# M_16PWM.net
KiCad netlist of a schematic drawn in EAGLE
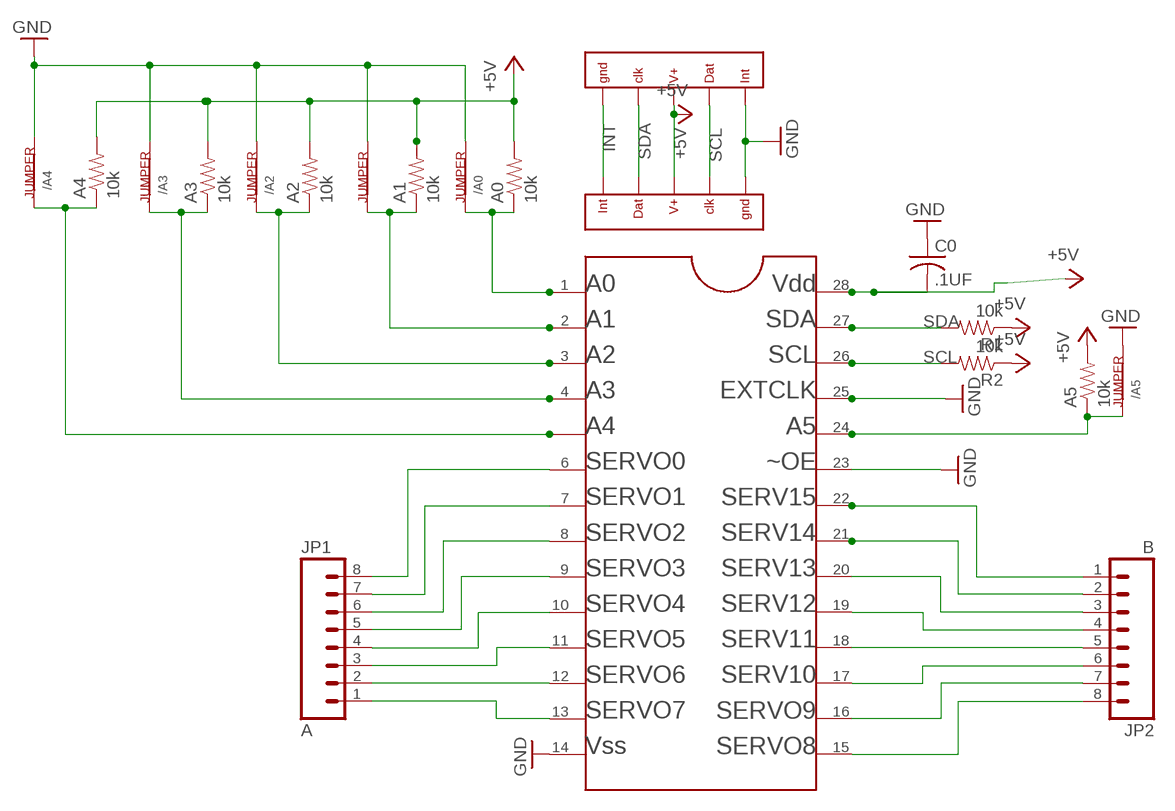
[diagram p0: schematic, sheet 1]

(export (version "E")
  (design (tool "Eeschema 10.0.6"))
  (components
    (comp (ref "/A0")
      (value "JUMPER")
      (footprint "eagle-import:JUMPER")
      (libsource (lib "eagle-import") (part "JUMPER"))
    )
    (comp (ref "/A1")
      (value "JUMPER")
      (footprint "eagle-import:JUMPER")
      (libsource (lib "eagle-import") (part "JUMPER"))
    )
    (comp (ref "/A2")
      (value "JUMPER")
      (footprint "eagle-import:JUMPER")
      (libsource (lib "eagle-import") (part "JUMPER"))
    )
    (comp (ref "/A3")
      (value "JUMPER")
      (footprint "eagle-import:JUMPER")
      (libsource (lib "eagle-import") (part "JUMPER"))
    )
    (comp (ref "/A4")
      (value "JUMPER")
      (footprint "eagle-import:JUMPER")
      (libsource (lib "eagle-import") (part "JUMPER"))
    )
    (comp (ref "/A5")
      (value "JUMPER")
      (footprint "eagle-import:JUMPER")
      (libsource (lib "eagle-import") (part "JUMPER"))
    )
    (comp (ref "A0")
      (value "10k")
      (footprint "eagle-import:0402-RES")
      (libsource (lib "eagle-import") (part "RESISTOR0402-RES"))
    )
    (comp (ref "A1")
      (value "10k")
      (footprint "eagle-import:0402-RES")
      (libsource (lib "eagle-import") (part "RESISTOR0402-RES"))
    )
    (comp (ref "A2")
      (value "10k")
      (footprint "eagle-import:0402-RES")
      (libsource (lib "eagle-import") (part "RESISTOR0402-RES"))
    )
    (comp (ref "A3")
      (value "10k")
      (footprint "eagle-import:0402-RES")
      (libsource (lib "eagle-import") (part "RESISTOR0402-RES"))
    )
    (comp (ref "A4")
      (value "10k")
      (footprint "eagle-import:0402-RES")
      (libsource (lib "eagle-import") (part "RESISTOR0402-RES"))
    )
    (comp (ref "A5")
      (value "10k")
      (footprint "eagle-import:0402-RES")
      (libsource (lib "eagle-import") (part "RESISTOR0402-RES"))
    )
    (comp (ref "C0")
      (value ".1UF")
      (footprint "eagle-import:C0603")
      (libsource (lib "eagle-import") (part "C-USC0603"))
    )
    (comp (ref "JP1")
      (value "A")
      (footprint "eagle-import:1X08")
      (libsource (lib "eagle-import") (part "M081X08"))
    )
    (comp (ref "JP2")
      (value "B")
      (footprint "eagle-import:1X08")
      (libsource (lib "eagle-import") (part "M081X08"))
    )
    (comp (ref "R1")
      (value "10k")
      (footprint "eagle-import:0402-RES")
      (libsource (lib "eagle-import") (part "RESISTOR0402-RES"))
    )
    (comp (ref "R2")
      (value "10k")
      (footprint "eagle-import:0402-RES")
      (libsource (lib "eagle-import") (part "RESISTOR0402-RES"))
    )
    (comp (ref "U$1")
      (value "PCA9685PW")
      (footprint "eagle-import:TSSOP28")
      (libsource (lib "eagle-import") (part "PCA9685PW"))
    )
    (comp (ref "U$2")
      (value "050-5")
      (footprint "eagle-import:050-5")
      (libsource (lib "eagle-import") (part "050-5"))
    )
    (comp (ref "U$3")
      (value "050-5")
      (footprint "eagle-import:050-5")
      (libsource (lib "eagle-import") (part "050-5"))
    )
  )
  (nets
    (net (code "1") (name "+5V") (class "Default")
      (node (ref "A0") (pin "2") (pinfunction "2_2") (pintype "passive"))
      (node (ref "A1") (pin "2") (pinfunction "2_2") (pintype "passive"))
      (node (ref "A2") (pin "2") (pinfunction "2_2") (pintype "passive"))
      (node (ref "A3") (pin "2") (pinfunction "2_2") (pintype "passive"))
      (node (ref "A4") (pin "2") (pinfunction "2_2") (pintype "passive"))
      (node (ref "A5") (pin "2") (pinfunction "2_2") (pintype "passive"))
      (node (ref "C0") (pin "2") (pinfunction "2_2") (pintype "passive"))
      (node (ref "R1") (pin "1") (pinfunction "1_1") (pintype "passive"))
      (node (ref "R2") (pin "1") (pinfunction "1_1") (pintype "passive"))
      (node (ref "U$1") (pin "28") (pinfunction "P$28_28") (pintype "bidirectional"))
      (node (ref "U$2") (pin "P$3") (pinfunction "P$3_P$3") (pintype "bidirectional"))
      (node (ref "U$3") (pin "P$3") (pinfunction "P$3_P$3") (pintype "bidirectional"))
    )
    (net (code "2") (name "/INT") (class "Default")
      (node (ref "U$2") (pin "P$1") (pinfunction "P$1_P$1") (pintype "bidirectional"))
      (node (ref "U$3") (pin "P$5") (pinfunction "P$5_P$5") (pintype "bidirectional"))
    )
    (net (code "3") (name "/SCL") (class "Default")
      (node (ref "R2") (pin "2") (pinfunction "2_2") (pintype "passive"))
      (node (ref "U$1") (pin "26") (pinfunction "P$26_26") (pintype "bidirectional"))
      (node (ref "U$2") (pin "P$4") (pinfunction "P$4_P$4") (pintype "bidirectional"))
      (node (ref "U$3") (pin "P$2") (pinfunction "P$2_P$2") (pintype "bidirectional"))
    )
    (net (code "4") (name "/SDA") (class "Default")
      (node (ref "R1") (pin "2") (pinfunction "2_2") (pintype "passive"))
      (node (ref "U$1") (pin "27") (pinfunction "P$27_27") (pintype "bidirectional"))
      (node (ref "U$2") (pin "P$2") (pinfunction "P$2_P$2") (pintype "bidirectional"))
      (node (ref "U$3") (pin "P$4") (pinfunction "P$4_P$4") (pintype "bidirectional"))
    )
    (net (code "5") (name "GND") (class "Default")
      (node (ref "/A0") (pin "2") (pinfunction "P$2_2") (pintype "bidirectional"))
      (node (ref "/A1") (pin "2") (pinfunction "P$2_2") (pintype "bidirectional"))
      (node (ref "/A2") (pin "2") (pinfunction "P$2_2") (pintype "bidirectional"))
      (node (ref "/A3") (pin "2") (pinfunction "P$2_2") (pintype "bidirectional"))
      (node (ref "/A4") (pin "2") (pinfunction "P$2_2") (pintype "bidirectional"))
      (node (ref "/A5") (pin "2") (pinfunction "P$2_2") (pintype "bidirectional"))
      (node (ref "C0") (pin "1") (pinfunction "1_1") (pintype "passive"))
      (node (ref "U$1") (pin "14") (pinfunction "P$14_14") (pintype "bidirectional"))
      (node (ref "U$1") (pin "23") (pinfunction "P$23_23") (pintype "bidirectional"))
      (node (ref "U$1") (pin "25") (pinfunction "P$25_25") (pintype "bidirectional"))
      (node (ref "U$2") (pin "P$5") (pinfunction "P$5_P$5") (pintype "bidirectional"))
      (node (ref "U$3") (pin "P$1") (pinfunction "P$1_P$1") (pintype "bidirectional"))
    )
    (net (code "6") (name "Net-(/A0-P$1)") (class "Default")
      (node (ref "/A0") (pin "1") (pinfunction "P$1_1") (pintype "bidirectional"))
      (node (ref "A0") (pin "1") (pinfunction "1_1") (pintype "passive"))
      (node (ref "U$1") (pin "1") (pinfunction "P$1_1") (pintype "bidirectional"))
    )
    (net (code "7") (name "Net-(/A1-P$1)") (class "Default")
      (node (ref "/A1") (pin "1") (pinfunction "P$1_1") (pintype "bidirectional"))
      (node (ref "A1") (pin "1") (pinfunction "1_1") (pintype "passive"))
      (node (ref "U$1") (pin "2") (pinfunction "P$2_2") (pintype "bidirectional"))
    )
    (net (code "8") (name "Net-(/A2-P$1)") (class "Default")
      (node (ref "/A2") (pin "1") (pinfunction "P$1_1") (pintype "bidirectional"))
      (node (ref "A2") (pin "1") (pinfunction "1_1") (pintype "passive"))
      (node (ref "U$1") (pin "3") (pinfunction "P$3_3") (pintype "bidirectional"))
    )
    (net (code "9") (name "Net-(/A3-P$1)") (class "Default")
      (node (ref "/A3") (pin "1") (pinfunction "P$1_1") (pintype "bidirectional"))
      (node (ref "A3") (pin "1") (pinfunction "1_1") (pintype "passive"))
      (node (ref "U$1") (pin "4") (pinfunction "P$4_4") (pintype "bidirectional"))
    )
    (net (code "10") (name "Net-(/A4-P$1)") (class "Default")
      (node (ref "/A4") (pin "1") (pinfunction "P$1_1") (pintype "bidirectional"))
      (node (ref "A4") (pin "1") (pinfunction "1_1") (pintype "passive"))
      (node (ref "U$1") (pin "5") (pinfunction "P$5_5") (pintype "bidirectional"))
    )
    (net (code "11") (name "Net-(/A5-P$1)") (class "Default")
      (node (ref "/A5") (pin "1") (pinfunction "P$1_1") (pintype "bidirectional"))
      (node (ref "A5") (pin "1") (pinfunction "1_1") (pintype "passive"))
      (node (ref "U$1") (pin "24") (pinfunction "P$24_24") (pintype "bidirectional"))
    )
    (net (code "12") (name "Net-(U$1-P$6)") (class "Default")
      (node (ref "JP1") (pin "8") (pinfunction "8_8") (pintype "passive"))
      (node (ref "U$1") (pin "6") (pinfunction "P$6_6") (pintype "bidirectional"))
    )
    (net (code "13") (name "Net-(U$1-P$7)") (class "Default")
      (node (ref "JP1") (pin "7") (pinfunction "7_7") (pintype "passive"))
      (node (ref "U$1") (pin "7") (pinfunction "P$7_7") (pintype "bidirectional"))
    )
    (net (code "14") (name "Net-(U$1-P$8)") (class "Default")
      (node (ref "JP1") (pin "6") (pinfunction "6_6") (pintype "passive"))
      (node (ref "U$1") (pin "8") (pinfunction "P$8_8") (pintype "bidirectional"))
    )
    (net (code "15") (name "Net-(U$1-P$9)") (class "Default")
      (node (ref "JP1") (pin "5") (pinfunction "5_5") (pintype "passive"))
      (node (ref "U$1") (pin "9") (pinfunction "P$9_9") (pintype "bidirectional"))
    )
    (net (code "16") (name "Net-(U$1-P$10)") (class "Default")
      (node (ref "JP1") (pin "4") (pinfunction "4_4") (pintype "passive"))
      (node (ref "U$1") (pin "10") (pinfunction "P$10_10") (pintype "bidirectional"))
    )
    (net (code "17") (name "Net-(U$1-P$11)") (class "Default")
      (node (ref "JP1") (pin "3") (pinfunction "3_3") (pintype "passive"))
      (node (ref "U$1") (pin "11") (pinfunction "P$11_11") (pintype "bidirectional"))
    )
    (net (code "18") (name "Net-(U$1-P$12)") (class "Default")
      (node (ref "JP1") (pin "2") (pinfunction "2_2") (pintype "passive"))
      (node (ref "U$1") (pin "12") (pinfunction "P$12_12") (pintype "bidirectional"))
    )
    (net (code "19") (name "Net-(U$1-P$13)") (class "Default")
      (node (ref "JP1") (pin "1") (pinfunction "1_1") (pintype "passive"))
      (node (ref "U$1") (pin "13") (pinfunction "P$13_13") (pintype "bidirectional"))
    )
    (net (code "20") (name "Net-(U$1-P$15)") (class "Default")
      (node (ref "JP2") (pin "8") (pinfunction "8_8") (pintype "passive"))
      (node (ref "U$1") (pin "15") (pinfunction "P$15_15") (pintype "bidirectional"))
    )
    (net (code "21") (name "Net-(U$1-P$16)") (class "Default")
      (node (ref "JP2") (pin "7") (pinfunction "7_7") (pintype "passive"))
      (node (ref "U$1") (pin "16") (pinfunction "P$16_16") (pintype "bidirectional"))
    )
    (net (code "22") (name "Net-(U$1-P$17)") (class "Default")
      (node (ref "JP2") (pin "6") (pinfunction "6_6") (pintype "passive"))
      (node (ref "U$1") (pin "17") (pinfunction "P$17_17") (pintype "bidirectional"))
    )
    (net (code "23") (name "Net-(U$1-P$18)") (class "Default")
      (node (ref "JP2") (pin "5") (pinfunction "5_5") (pintype "passive"))
      (node (ref "U$1") (pin "18") (pinfunction "P$18_18") (pintype "bidirectional"))
    )
    (net (code "24") (name "Net-(U$1-P$19)") (class "Default")
      (node (ref "JP2") (pin "4") (pinfunction "4_4") (pintype "passive"))
      (node (ref "U$1") (pin "19") (pinfunction "P$19_19") (pintype "bidirectional"))
    )
    (net (code "25") (name "Net-(U$1-P$20)") (class "Default")
      (node (ref "JP2") (pin "3") (pinfunction "3_3") (pintype "passive"))
      (node (ref "U$1") (pin "20") (pinfunction "P$20_20") (pintype "bidirectional"))
    )
    (net (code "26") (name "Net-(U$1-P$21)") (class "Default")
      (node (ref "JP2") (pin "2") (pinfunction "2_2") (pintype "passive"))
      (node (ref "U$1") (pin "21") (pinfunction "P$21_21") (pintype "bidirectional"))
    )
    (net (code "27") (name "Net-(U$1-P$22)") (class "Default")
      (node (ref "JP2") (pin "1") (pinfunction "1_1") (pintype "passive"))
      (node (ref "U$1") (pin "22") (pinfunction "P$22_22") (pintype "bidirectional"))
    )
  )
)
